# Infrared.net
KiCad netlist of a schematic drawn in Altium Designer
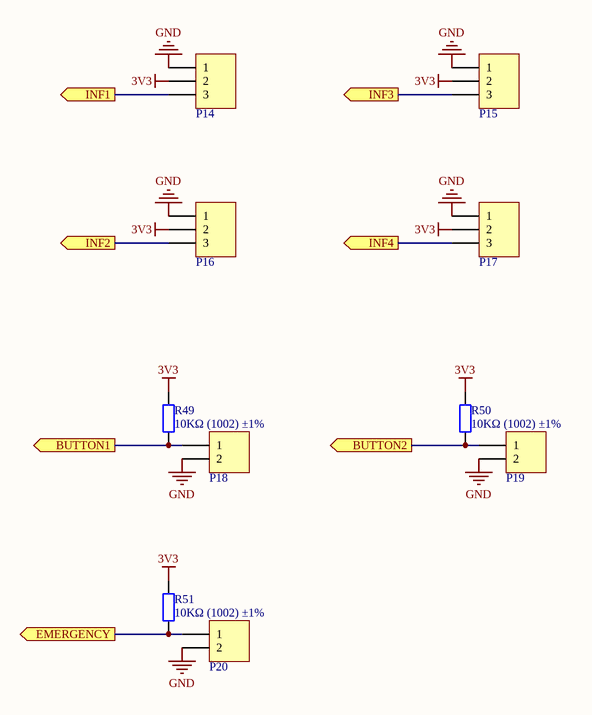
[diagram p0: Infrared.SchDoc]

(export (version "E")
  (design (tool "Eeschema 10.0.6"))
  (components
    (comp (ref "P14")
      (value "B3B-PH-SM4-TB(LF)(SN)")
      (footprint "B3B-PH-SM4-TB(LF)(SN)")
      (description "CONN HEADER PH TOP 3POS 2MM SMD")
      (fields (field (name "MANUFACTURER") "JST Sales America Inc."))
      (libsource (lib "RoboteX") (part "Header 3"))
    )
    (comp (ref "P15")
      (value "B3B-PH-SM4-TB(LF)(SN)")
      (footprint "B3B-PH-SM4-TB(LF)(SN)")
      (description "CONN HEADER PH TOP 3POS 2MM SMD")
      (fields (field (name "MANUFACTURER") "JST Sales America Inc."))
      (libsource (lib "RoboteX") (part "Header 3"))
    )
    (comp (ref "P16")
      (value "B3B-PH-SM4-TB(LF)(SN)")
      (footprint "B3B-PH-SM4-TB(LF)(SN)")
      (description "CONN HEADER PH TOP 3POS 2MM SMD")
      (fields (field (name "MANUFACTURER") "JST Sales America Inc."))
      (libsource (lib "RoboteX") (part "Header 3"))
    )
    (comp (ref "P17")
      (value "B3B-PH-SM4-TB(LF)(SN)")
      (footprint "B3B-PH-SM4-TB(LF)(SN)")
      (description "CONN HEADER PH TOP 3POS 2MM SMD")
      (fields (field (name "MANUFACTURER") "JST Sales America Inc."))
      (libsource (lib "RoboteX") (part "Header 3"))
    )
    (comp (ref "P18")
      (value "B2B-PH-SM4-TB(LF)(SN)")
      (footprint "B2B-PH-SM4-TB(LF)(SN)")
      (description "CONN HEADER PH TOP 2POS 2MM SMD")
      (fields (field (name "MANUFACTURER") "JST Sales America Inc."))
      (libsource (lib "RoboteX") (part "Header 2 POS"))
    )
    (comp (ref "P19")
      (value "B2B-PH-SM4-TB(LF)(SN)")
      (footprint "B2B-PH-SM4-TB(LF)(SN)")
      (description "CONN HEADER PH TOP 2POS 2MM SMD")
      (fields (field (name "MANUFACTURER") "JST Sales America Inc."))
      (libsource (lib "RoboteX") (part "Header 2 POS"))
    )
    (comp (ref "P20")
      (value "B2B-PH-SM4-TB(LF)(SN)")
      (footprint "B2B-PH-SM4-TB(LF)(SN)")
      (description "CONN HEADER PH TOP 2POS 2MM SMD")
      (fields (field (name "MANUFACTURER") "JST Sales America Inc."))
      (libsource (lib "RoboteX") (part "Header 2 POS"))
    )
    (comp (ref "R49")
      (value "10KΩ (1002) ±1%")
      (footprint "0603_R")
      (description "贴片电阻")
      (libsource (lib "Miscellaneous Devices LC") (part "0603 10KΩ (1002) 1%"))
    )
    (comp (ref "R50")
      (value "10KΩ (1002) ±1%")
      (footprint "0603_R")
      (description "贴片电阻")
      (libsource (lib "Miscellaneous Devices LC") (part "0603 10KΩ (1002) 1%"))
    )
    (comp (ref "R51")
      (value "10KΩ (1002) ±1%")
      (footprint "0603_R")
      (description "贴片电阻")
      (libsource (lib "Miscellaneous Devices LC") (part "0603 10KΩ (1002) 1%"))
    )
  )
  (nets
    (net (code "1") (name "/BUTTON1") (class "Default")
      (node (ref "P18") (pin "1") (pinfunction "1_1") (pintype "passive"))
      (node (ref "R49") (pin "1") (pinfunction "1_1") (pintype "passive"))
    )
    (net (code "2") (name "/BUTTON2") (class "Default")
      (node (ref "P19") (pin "1") (pinfunction "1_1") (pintype "passive"))
      (node (ref "R50") (pin "1") (pinfunction "1_1") (pintype "passive"))
    )
    (net (code "3") (name "/EMERGENCY") (class "Default")
      (node (ref "P20") (pin "1") (pinfunction "1_1") (pintype "passive"))
      (node (ref "R51") (pin "1") (pinfunction "1_1") (pintype "passive"))
    )
    (net (code "4") (name "/INF1") (class "Default")
      (node (ref "P14") (pin "3") (pinfunction "3_3") (pintype "passive"))
    )
    (net (code "5") (name "/INF2") (class "Default")
      (node (ref "P16") (pin "3") (pinfunction "3_3") (pintype "passive"))
    )
    (net (code "6") (name "/INF3") (class "Default")
      (node (ref "P15") (pin "3") (pinfunction "3_3") (pintype "passive"))
    )
    (net (code "7") (name "/INF4") (class "Default")
      (node (ref "P17") (pin "3") (pinfunction "3_3") (pintype "passive"))
    )
    (net (code "8") (name "3V3") (class "Default")
      (node (ref "P14") (pin "2") (pinfunction "2_2") (pintype "passive"))
      (node (ref "P15") (pin "2") (pinfunction "2_2") (pintype "passive"))
      (node (ref "P16") (pin "2") (pinfunction "2_2") (pintype "passive"))
      (node (ref "P17") (pin "2") (pinfunction "2_2") (pintype "passive"))
      (node (ref "R49") (pin "2") (pinfunction "2_2") (pintype "passive"))
      (node (ref "R50") (pin "2") (pinfunction "2_2") (pintype "passive"))
      (node (ref "R51") (pin "2") (pinfunction "2_2") (pintype "passive"))
    )
    (net (code "9") (name "GND") (class "Default")
      (node (ref "P14") (pin "1") (pinfunction "1_1") (pintype "passive"))
      (node (ref "P15") (pin "1") (pinfunction "1_1") (pintype "passive"))
      (node (ref "P16") (pin "1") (pinfunction "1_1") (pintype "passive"))
      (node (ref "P17") (pin "1") (pinfunction "1_1") (pintype "passive"))
      (node (ref "P18") (pin "2") (pinfunction "2_2") (pintype "passive"))
      (node (ref "P19") (pin "2") (pinfunction "2_2") (pintype "passive"))
      (node (ref "P20") (pin "2") (pinfunction "2_2") (pintype "passive"))
    )
  )
)
